# untitled.net
KiCad netlist of a schematic drawn in EAGLE
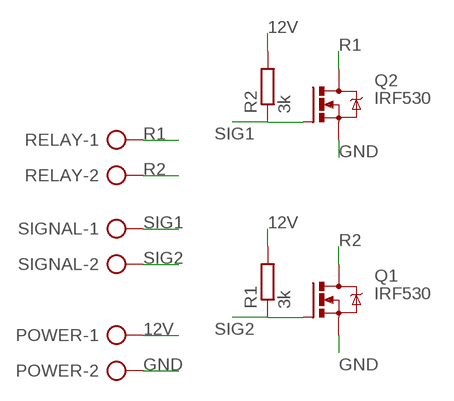
[diagram p0: schematic, sheet 1]

(export (version "E")
  (design (tool "Eeschema 10.0.6"))
  (components
    (comp (ref "POWER")
      (value "AK300/2")
      (footprint "eagle-import:AK300_2")
      (libsource (lib "eagle-import") (part "AK300/2"))
    )
    (comp (ref "Q1")
      (value "IRF530")
      (footprint "eagle-import:TO220BV")
      (libsource (lib "eagle-import") (part "IRF530"))
    )
    (comp (ref "Q2")
      (value "IRF530")
      (footprint "eagle-import:TO220BV")
      (libsource (lib "eagle-import") (part "IRF530"))
    )
    (comp (ref "R1")
      (value "3k")
      (footprint "eagle-import:0204_7")
      (libsource (lib "eagle-import") (part "R-EU_0204/7"))
    )
    (comp (ref "R2")
      (value "3k")
      (footprint "eagle-import:0204_7")
      (libsource (lib "eagle-import") (part "R-EU_0204/7"))
    )
    (comp (ref "RELAY")
      (value "AK300/2")
      (footprint "eagle-import:AK300_2")
      (libsource (lib "eagle-import") (part "AK300/2"))
    )
    (comp (ref "SIGNAL")
      (value "AK300/2")
      (footprint "eagle-import:AK300_2")
      (libsource (lib "eagle-import") (part "AK300/2"))
    )
  )
  (nets
    (net (code "1") (name "/12V") (class "Default")
      (node (ref "POWER") (pin "1") (pinfunction "KL_1") (pintype "passive"))
      (node (ref "R1") (pin "2") (pinfunction "2_2") (pintype "passive"))
      (node (ref "R2") (pin "2") (pinfunction "2_2") (pintype "passive"))
    )
    (net (code "2") (name "/GND") (class "Default")
      (node (ref "POWER") (pin "2") (pinfunction "KL_2") (pintype "passive"))
      (node (ref "Q1") (pin "S") (pinfunction "S_S") (pintype "passive"))
      (node (ref "Q2") (pin "S") (pinfunction "S_S") (pintype "passive"))
    )
    (net (code "3") (name "/R1") (class "Default")
      (node (ref "Q2") (pin "D") (pinfunction "D_D") (pintype "passive"))
      (node (ref "RELAY") (pin "1") (pinfunction "KL_1") (pintype "passive"))
    )
    (net (code "4") (name "/R2") (class "Default")
      (node (ref "Q1") (pin "D") (pinfunction "D_D") (pintype "passive"))
      (node (ref "RELAY") (pin "2") (pinfunction "KL_2") (pintype "passive"))
    )
    (net (code "5") (name "/SIG1") (class "Default")
      (node (ref "Q2") (pin "G") (pinfunction "G_G") (pintype "passive"))
      (node (ref "R2") (pin "1") (pinfunction "1_1") (pintype "passive"))
      (node (ref "SIGNAL") (pin "1") (pinfunction "KL_1") (pintype "passive"))
    )
    (net (code "6") (name "/SIG2") (class "Default")
      (node (ref "Q1") (pin "G") (pinfunction "G_G") (pintype "passive"))
      (node (ref "R1") (pin "1") (pinfunction "1_1") (pintype "passive"))
      (node (ref "SIGNAL") (pin "2") (pinfunction "KL_2") (pintype "passive"))
    )
  )
)
